# Sheet1.net
KiCad netlist of a schematic drawn in Altium Designer
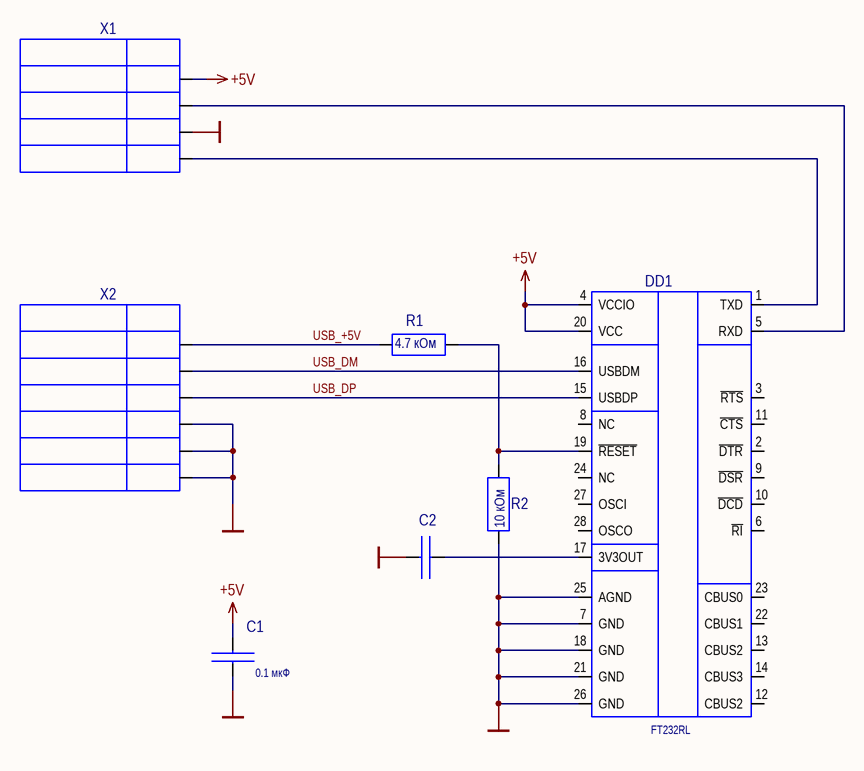
[diagram p0: Sheet1.SchDoc]

(export (version "E")
  (design (tool "Eeschema 10.0.6"))
  (components
    (comp (ref "C1")
      (value "0.1 мкФ")
      (footprint "C0805")
      (fields (field (name "TOLERANCE") "5%") (field (name "Comment") "C_2"))
      (libsource (lib "tsb_lib") (part "C_2"))
    )
    (comp (ref "C2")
      (value "C_2")
      (footprint "C0805")
      (fields (field (name "MANUFACTURER") "ф. Kemet") (field (name "TOLERANCE") "5%"))
      (libsource (lib "ib_lib") (part "C_2"))
    )
    (comp (ref "DD1")
      (value "FT232RL")
      (footprint "SSOP28-LD")
      (fields (field (name "MANUFACTURER") "ф. FTDI"))
      (libsource (lib "ib_lib") (part "FT232RL"))
    )
    (comp (ref "R1")
      (value "4.7 кОм")
      (footprint "C0805")
      (fields (field (name "TOLERANCE") "5%") (field (name "Comment") "R_1"))
      (libsource (lib "stend_plate") (part "R_1"))
    )
    (comp (ref "R2")
      (value "10 кОм")
      (footprint "C0805")
      (fields (field (name "TOLERANCE") "5%") (field (name "Comment") "R_1"))
      (libsource (lib "stend_plate") (part "R_1"))
    )
    (comp (ref "X1")
      (value "PLS4")
      (footprint "HDR1X4")
      (fields (field (name "MANUFACTURER") "ф. Ningbo Zhenqin Electronic"))
      (libsource (lib "Common_lib") (part "PLS4"))
    )
    (comp (ref "X2")
      (value "USB Type B")
      (footprint "USB Type B")
      (libsource (lib "ml_lib") (part "USB Type B"))
    )
  )
  (nets
    (net (code "1") (name "+5V") (class "Default")
      (node (ref "C1") (pin "1") (pintype "passive"))
      (node (ref "DD1") (pin "20") (pinfunction "VCC_20") (pintype "passive"))
      (node (ref "DD1") (pin "4") (pinfunction "VCCIO_4") (pintype "passive"))
      (node (ref "X1") (pin "1") (pintype "passive"))
    )
    (net (code "2") (name "/USB_+5V") (class "Default")
      (node (ref "R1") (pin "1") (pintype "passive"))
      (node (ref "X2") (pin "1") (pintype "passive"))
    )
    (net (code "3") (name "/USB_DM") (class "Default")
      (node (ref "DD1") (pin "16") (pinfunction "USBDM_16") (pintype "passive"))
      (node (ref "X2") (pin "2") (pintype "passive"))
    )
    (net (code "4") (name "/USB_DP") (class "Default")
      (node (ref "DD1") (pin "15") (pinfunction "USBDP_15") (pintype "passive"))
      (node (ref "X2") (pin "3") (pintype "passive"))
    )
    (net (code "5") (name "GND") (class "Default")
      (node (ref "C1") (pin "2") (pintype "passive"))
      (node (ref "C2") (pin "2") (pintype "passive"))
      (node (ref "DD1") (pin "18") (pinfunction "GND_18") (pintype "passive"))
      (node (ref "DD1") (pin "21") (pinfunction "GND_21") (pintype "passive"))
      (node (ref "DD1") (pin "25") (pinfunction "AGND_25") (pintype "passive"))
      (node (ref "DD1") (pin "26") (pinfunction "GND_26") (pintype "passive"))
      (node (ref "DD1") (pin "7") (pinfunction "GND_7") (pintype "passive"))
      (node (ref "R2") (pin "2") (pintype "passive"))
      (node (ref "X1") (pin "3") (pintype "passive"))
      (node (ref "X2") (pin "4") (pintype "passive"))
      (node (ref "X2") (pin "5") (pintype "passive"))
      (node (ref "X2") (pin "6") (pintype "passive"))
    )
    (net (code "6") (name "Net-(DD1-3V3OUT)") (class "Default")
      (node (ref "C2") (pin "1") (pintype "passive"))
      (node (ref "DD1") (pin "17") (pinfunction "3V3OUT_17") (pintype "passive"))
    )
    (net (code "7") (name "Net-(DD1-RESET)") (class "Default")
      (node (ref "DD1") (pin "19") (pinfunction "RESET_19") (pintype "passive"))
      (node (ref "R1") (pin "2") (pintype "passive"))
      (node (ref "R2") (pin "1") (pintype "passive"))
    )
    (net (code "8") (name "Net-(DD1-RXD)") (class "Default")
      (node (ref "DD1") (pin "5") (pinfunction "RXD_5") (pintype "passive"))
      (node (ref "X1") (pin "2") (pintype "passive"))
    )
    (net (code "9") (name "Net-(DD1-TXD)") (class "Default")
      (node (ref "DD1") (pin "1") (pinfunction "TXD_1") (pintype "passive"))
      (node (ref "X1") (pin "4") (pintype "passive"))
    )
    (net (code "10") (name "unconnected-(DD1-CBUS0-Pad23)") (class "Default")
      (node (ref "DD1") (pin "23") (pinfunction "CBUS0_23") (pintype "passive"))
    )
    (net (code "11") (name "unconnected-(DD1-CBUS1-Pad22)") (class "Default")
      (node (ref "DD1") (pin "22") (pinfunction "CBUS1_22") (pintype "passive"))
    )
    (net (code "12") (name "unconnected-(DD1-CBUS2-Pad12)") (class "Default")
      (node (ref "DD1") (pin "12") (pinfunction "CBUS2_12") (pintype "passive"))
    )
    (net (code "13") (name "unconnected-(DD1-CBUS2-Pad13)") (class "Default")
      (node (ref "DD1") (pin "13") (pinfunction "CBUS2_13") (pintype "passive"))
    )
    (net (code "14") (name "unconnected-(DD1-CBUS3-Pad14)") (class "Default")
      (node (ref "DD1") (pin "14") (pinfunction "CBUS3_14") (pintype "passive"))
    )
    (net (code "15") (name "unconnected-(DD1-CTS-Pad11)") (class "Default")
      (node (ref "DD1") (pin "11") (pinfunction "CTS_11") (pintype "passive"))
    )
    (net (code "16") (name "unconnected-(DD1-DCD-Pad10)") (class "Default")
      (node (ref "DD1") (pin "10") (pinfunction "DCD_10") (pintype "passive"))
    )
    (net (code "17") (name "unconnected-(DD1-DSR-Pad9)") (class "Default")
      (node (ref "DD1") (pin "9") (pinfunction "DSR_9") (pintype "passive"))
    )
    (net (code "18") (name "unconnected-(DD1-DTR-Pad2)") (class "Default")
      (node (ref "DD1") (pin "2") (pinfunction "DTR_2") (pintype "passive"))
    )
    (net (code "19") (name "unconnected-(DD1-NC-Pad8)") (class "Default")
      (node (ref "DD1") (pin "8") (pinfunction "NC_8") (pintype "passive"))
    )
    (net (code "20") (name "unconnected-(DD1-NC-Pad24)") (class "Default")
      (node (ref "DD1") (pin "24") (pinfunction "NC_24") (pintype "passive"))
    )
    (net (code "21") (name "unconnected-(DD1-OSCI-Pad27)") (class "Default")
      (node (ref "DD1") (pin "27") (pinfunction "OSCI_27") (pintype "passive"))
    )
    (net (code "22") (name "unconnected-(DD1-OSCO-Pad28)") (class "Default")
      (node (ref "DD1") (pin "28") (pinfunction "OSCO_28") (pintype "passive"))
    )
    (net (code "23") (name "unconnected-(DD1-RI-Pad6)") (class "Default")
      (node (ref "DD1") (pin "6") (pinfunction "RI_6") (pintype "passive"))
    )
    (net (code "24") (name "unconnected-(DD1-RTS-Pad3)") (class "Default")
      (node (ref "DD1") (pin "3") (pinfunction "RTS_3") (pintype "passive"))
    )
  )
)
